# STM32F103_DEBUGGER.net
KiCad netlist of a schematic drawn in Altium Designer
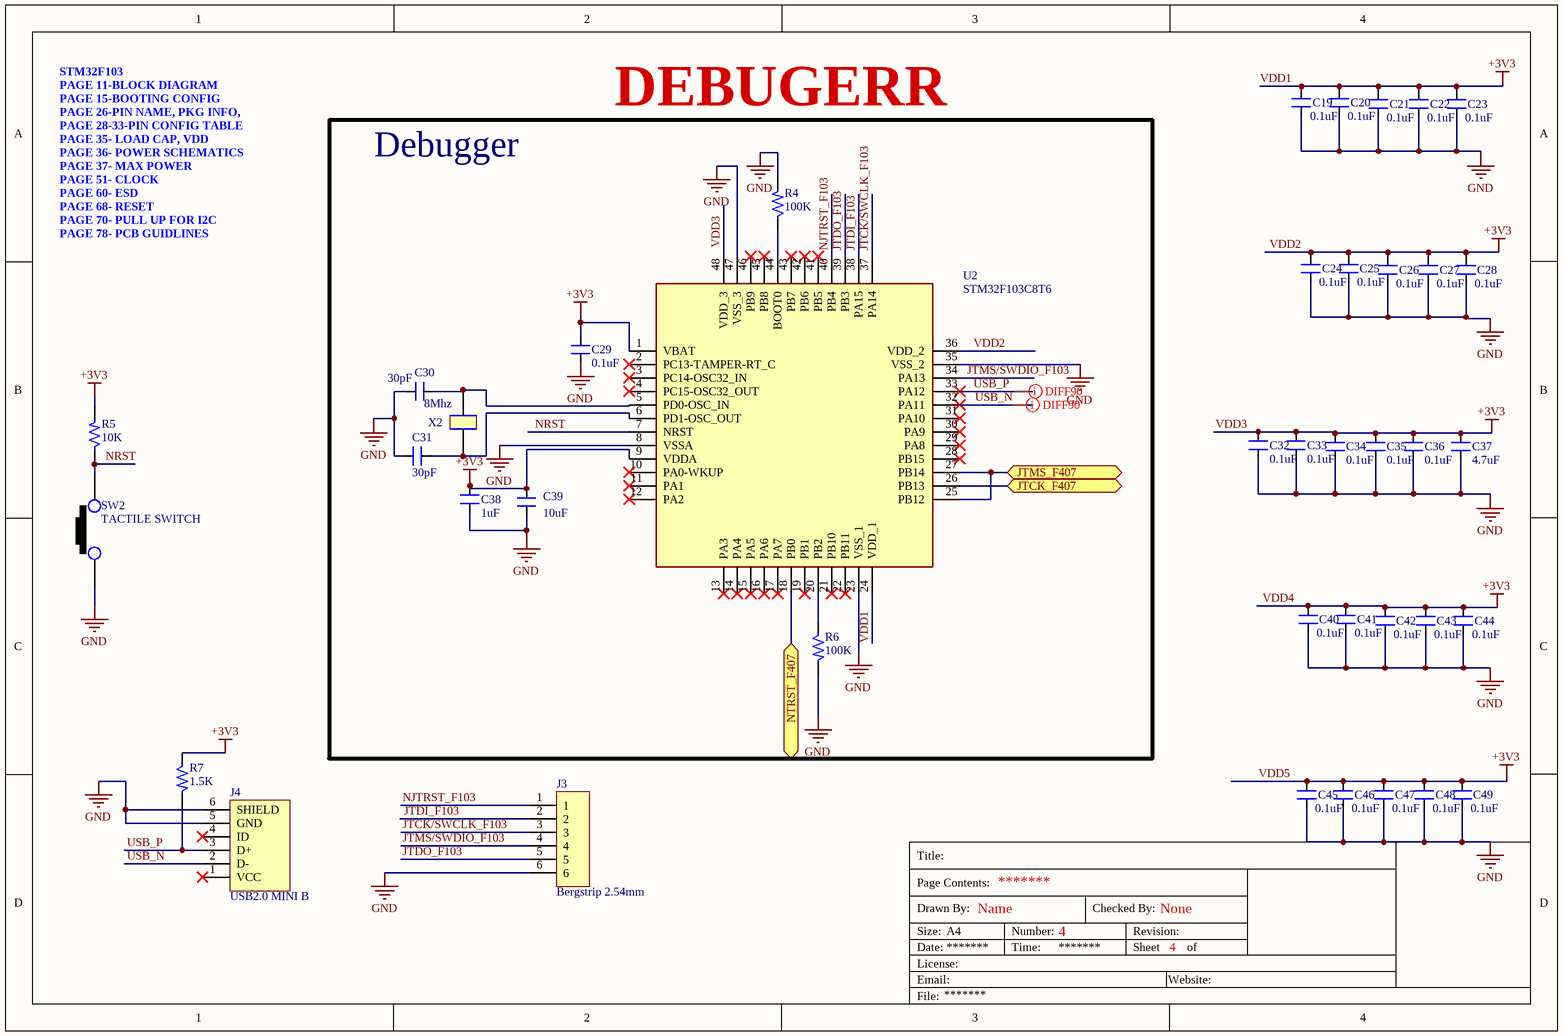
[diagram p0: STM32F103 DEBUGGER.SchDoc]

(export (version "E")
  (design (tool "Eeschema 10.0.6"))
  (components
    (comp (ref "C19")
      (value "0.1uF")
      (footprint "CAP_1206")
      (description "0.1µF ±5% 50V Ceramic Capacitor X7R 1206 (3216 Metric)")
      (fields
        (field (name "MANUFACTURER") "KEMET")
        (field (name "MANUFACTURER PART NUMBER") "C1206C104J5RACTU")
      )
      (libsource (lib "ESTEEMPCBLIB") (part "CAP_0.1uF-50V-5%-1206"))
    )
    (comp (ref "C20")
      (value "0.1uF")
      (footprint "CAP_1206")
      (description "0.1µF ±5% 50V Ceramic Capacitor X7R 1206 (3216 Metric)")
      (fields
        (field (name "MANUFACTURER") "KEMET")
        (field (name "MANUFACTURER PART NUMBER") "C1206C104J5RACTU")
      )
      (libsource (lib "ESTEEMPCBLIB") (part "CAP_0.1uF-50V-5%-1206"))
    )
    (comp (ref "C21")
      (value "0.1uF")
      (footprint "CAP_1206")
      (description "0.1µF ±5% 50V Ceramic Capacitor X7R 1206 (3216 Metric)")
      (fields
        (field (name "MANUFACTURER") "KEMET")
        (field (name "MANUFACTURER PART NUMBER") "C1206C104J5RACTU")
      )
      (libsource (lib "ESTEEMPCBLIB") (part "CAP_0.1uF-50V-5%-1206"))
    )
    (comp (ref "C22")
      (value "0.1uF")
      (footprint "CAP_1206")
      (description "0.1µF ±5% 50V Ceramic Capacitor X7R 1206 (3216 Metric)")
      (fields
        (field (name "MANUFACTURER") "KEMET")
        (field (name "MANUFACTURER PART NUMBER") "C1206C104J5RACTU")
      )
      (libsource (lib "ESTEEMPCBLIB") (part "CAP_0.1uF-50V-5%-1206"))
    )
    (comp (ref "C23")
      (value "0.1uF")
      (footprint "CAP_1206")
      (description "0.1µF ±5% 50V Ceramic Capacitor X7R 1206 (3216 Metric)")
      (fields
        (field (name "MANUFACTURER") "KEMET")
        (field (name "MANUFACTURER PART NUMBER") "C1206C104J5RACTU")
      )
      (libsource (lib "ESTEEMPCBLIB") (part "CAP_0.1uF-50V-5%-1206"))
    )
    (comp (ref "C24")
      (value "0.1uF")
      (footprint "CAP_1206")
      (description "0.1µF ±5% 50V Ceramic Capacitor X7R 1206 (3216 Metric)")
      (fields
        (field (name "MANUFACTURER") "KEMET")
        (field (name "MANUFACTURER PART NUMBER") "C1206C104J5RACTU")
      )
      (libsource (lib "ESTEEMPCBLIB") (part "CAP_0.1uF-50V-5%-1206"))
    )
    (comp (ref "C25")
      (value "0.1uF")
      (footprint "CAP_1206")
      (description "0.1µF ±5% 50V Ceramic Capacitor X7R 1206 (3216 Metric)")
      (fields
        (field (name "MANUFACTURER") "KEMET")
        (field (name "MANUFACTURER PART NUMBER") "C1206C104J5RACTU")
      )
      (libsource (lib "ESTEEMPCBLIB") (part "CAP_0.1uF-50V-5%-1206"))
    )
    (comp (ref "C26")
      (value "0.1uF")
      (footprint "CAP_1206")
      (description "0.1µF ±5% 50V Ceramic Capacitor X7R 1206 (3216 Metric)")
      (fields
        (field (name "MANUFACTURER") "KEMET")
        (field (name "MANUFACTURER PART NUMBER") "C1206C104J5RACTU")
      )
      (libsource (lib "ESTEEMPCBLIB") (part "CAP_0.1uF-50V-5%-1206"))
    )
    (comp (ref "C27")
      (value "0.1uF")
      (footprint "CAP_1206")
      (description "0.1µF ±5% 50V Ceramic Capacitor X7R 1206 (3216 Metric)")
      (fields
        (field (name "MANUFACTURER") "KEMET")
        (field (name "MANUFACTURER PART NUMBER") "C1206C104J5RACTU")
      )
      (libsource (lib "ESTEEMPCBLIB") (part "CAP_0.1uF-50V-5%-1206"))
    )
    (comp (ref "C28")
      (value "0.1uF")
      (footprint "CAP_1206")
      (description "0.1µF ±5% 50V Ceramic Capacitor X7R 1206 (3216 Metric)")
      (fields
        (field (name "MANUFACTURER") "KEMET")
        (field (name "MANUFACTURER PART NUMBER") "C1206C104J5RACTU")
      )
      (libsource (lib "ESTEEMPCBLIB") (part "CAP_0.1uF-50V-5%-1206"))
    )
    (comp (ref "C29")
      (value "0.1uF")
      (footprint "CAP_0805")
      (description "0.1µF ±10% 50V Ceramic Capacitor X7R 0805 (2012 Metric)")
      (fields
        (field (name "MANUFACTURER") "Samsung")
        (field (name "MANUFACTURER PART NUMBER") "CL21B104KBCNNNC")
      )
      (libsource (lib "ESTEEMPCBLIB") (part "CAP_0.1uF-50V-10%-0805"))
    )
    (comp (ref "C30")
      (value "30pF")
      (footprint "CAP_0805")
      (description "±10% 50V Ceramic Capacitor C0G, NP0 0805 (2012 Metric)")
      (fields
        (field (name "MANUFACTURER PART NUMBER") "C0805C300K5GAC7800")
        (field (name "MANUFACTURER") "KEMET")
      )
      (libsource (lib "ESTEEMPCBLIB") (part "CAP_30pF-50V-10%-0805"))
    )
    (comp (ref "C31")
      (value "30pF")
      (footprint "CAP_0805")
      (description "±10% 50V Ceramic Capacitor C0G, NP0 0805 (2012 Metric)")
      (fields
        (field (name "MANUFACTURER PART NUMBER") "C0805C300K5GAC7800")
        (field (name "MANUFACTURER") "KEMET")
      )
      (libsource (lib "ESTEEMPCBLIB") (part "CAP_30pF-50V-10%-0805"))
    )
    (comp (ref "C32")
      (value "0.1uF")
      (footprint "CAP_1206")
      (description "0.1µF ±5% 50V Ceramic Capacitor X7R 1206 (3216 Metric)")
      (fields
        (field (name "MANUFACTURER") "KEMET")
        (field (name "MANUFACTURER PART NUMBER") "C1206C104J5RACTU")
      )
      (libsource (lib "ESTEEMPCBLIB") (part "CAP_0.1uF-50V-5%-1206"))
    )
    (comp (ref "C33")
      (value "0.1uF")
      (footprint "CAP_1206")
      (description "0.1µF ±5% 50V Ceramic Capacitor X7R 1206 (3216 Metric)")
      (fields
        (field (name "MANUFACTURER") "KEMET")
        (field (name "MANUFACTURER PART NUMBER") "C1206C104J5RACTU")
      )
      (libsource (lib "ESTEEMPCBLIB") (part "CAP_0.1uF-50V-5%-1206"))
    )
    (comp (ref "C34")
      (value "0.1uF")
      (footprint "CAP_1206")
      (description "0.1µF ±5% 50V Ceramic Capacitor X7R 1206 (3216 Metric)")
      (fields
        (field (name "MANUFACTURER") "KEMET")
        (field (name "MANUFACTURER PART NUMBER") "C1206C104J5RACTU")
      )
      (libsource (lib "ESTEEMPCBLIB") (part "CAP_0.1uF-50V-5%-1206"))
    )
    (comp (ref "C35")
      (value "0.1uF")
      (footprint "CAP_1206")
      (description "0.1µF ±5% 50V Ceramic Capacitor X7R 1206 (3216 Metric)")
      (fields
        (field (name "MANUFACTURER") "KEMET")
        (field (name "MANUFACTURER PART NUMBER") "C1206C104J5RACTU")
      )
      (libsource (lib "ESTEEMPCBLIB") (part "CAP_0.1uF-50V-5%-1206"))
    )
    (comp (ref "C36")
      (value "0.1uF")
      (footprint "CAP_1206")
      (description "0.1µF ±5% 50V Ceramic Capacitor X7R 1206 (3216 Metric)")
      (fields
        (field (name "MANUFACTURER") "KEMET")
        (field (name "MANUFACTURER PART NUMBER") "C1206C104J5RACTU")
      )
      (libsource (lib "ESTEEMPCBLIB") (part "CAP_0.1uF-50V-5%-1206"))
    )
    (comp (ref "C37")
      (value "4.7uF")
      (footprint "CAP_0805")
      (description "4.7µF ±10% 50V Ceramic Capacitor X5R 0805 (2012 Metric)")
      (fields
        (field (name "MANUFACTURER") "Yageo")
        (field (name "MANUFACTURER PART NUMBER") "GRM21BR61H475KE51L")
      )
      (libsource (lib "ESTEEMPCBLIB") (part "CAP_4.7uF-50V-10%-0805"))
    )
    (comp (ref "C38")
      (value "1uF")
      (footprint "CAP_0805")
      (description "1µF ±5% 50V Ceramic Capacitor X7R 0805 (2012 Metric)")
      (fields
        (field (name "MANUFACTURER") "Samsung")
        (field (name "MANUFACTURER PART NUMBER") "CC0805JKX7R9BB105")
      )
      (libsource (lib "ESTEEMPCBLIB") (part "CAP_1uF-50V-5%-0805"))
    )
    (comp (ref "C39")
      (value "10uF")
      (footprint "CAP_1206")
      (description "10µF ±10% 50V Ceramic Capacitor X7R 1206 (3216 Metric)")
      (fields
        (field (name "MANUFACTURER") "KEMET")
        (field (name "MANUFACTURER PART NUMBER") "CL31B106KBHNNNE")
      )
      (libsource (lib "ESTEEMPCBLIB") (part "CAP_10uF-50V-10%-1206"))
    )
    (comp (ref "C40")
      (value "0.1uF")
      (footprint "CAP_1206")
      (description "0.1µF ±5% 50V Ceramic Capacitor X7R 1206 (3216 Metric)")
      (fields
        (field (name "MANUFACTURER") "KEMET")
        (field (name "MANUFACTURER PART NUMBER") "C1206C104J5RACTU")
      )
      (libsource (lib "ESTEEMPCBLIB") (part "CAP_0.1uF-50V-5%-1206"))
    )
    (comp (ref "C41")
      (value "0.1uF")
      (footprint "CAP_1206")
      (description "0.1µF ±5% 50V Ceramic Capacitor X7R 1206 (3216 Metric)")
      (fields
        (field (name "MANUFACTURER") "KEMET")
        (field (name "MANUFACTURER PART NUMBER") "C1206C104J5RACTU")
      )
      (libsource (lib "ESTEEMPCBLIB") (part "CAP_0.1uF-50V-5%-1206"))
    )
    (comp (ref "C42")
      (value "0.1uF")
      (footprint "CAP_1206")
      (description "0.1µF ±5% 50V Ceramic Capacitor X7R 1206 (3216 Metric)")
      (fields
        (field (name "MANUFACTURER") "KEMET")
        (field (name "MANUFACTURER PART NUMBER") "C1206C104J5RACTU")
      )
      (libsource (lib "ESTEEMPCBLIB") (part "CAP_0.1uF-50V-5%-1206"))
    )
    (comp (ref "C43")
      (value "0.1uF")
      (footprint "CAP_1206")
      (description "0.1µF ±5% 50V Ceramic Capacitor X7R 1206 (3216 Metric)")
      (fields
        (field (name "MANUFACTURER") "KEMET")
        (field (name "MANUFACTURER PART NUMBER") "C1206C104J5RACTU")
      )
      (libsource (lib "ESTEEMPCBLIB") (part "CAP_0.1uF-50V-5%-1206"))
    )
    (comp (ref "C44")
      (value "0.1uF")
      (footprint "CAP_1206")
      (description "0.1µF ±5% 50V Ceramic Capacitor X7R 1206 (3216 Metric)")
      (fields
        (field (name "MANUFACTURER") "KEMET")
        (field (name "MANUFACTURER PART NUMBER") "C1206C104J5RACTU")
      )
      (libsource (lib "ESTEEMPCBLIB") (part "CAP_0.1uF-50V-5%-1206"))
    )
    (comp (ref "C45")
      (value "0.1uF")
      (footprint "CAP_1206")
      (description "0.1µF ±5% 50V Ceramic Capacitor X7R 1206 (3216 Metric)")
      (fields
        (field (name "MANUFACTURER") "KEMET")
        (field (name "MANUFACTURER PART NUMBER") "C1206C104J5RACTU")
      )
      (libsource (lib "ESTEEMPCBLIB") (part "CAP_0.1uF-50V-5%-1206"))
    )
    (comp (ref "C46")
      (value "0.1uF")
      (footprint "CAP_1206")
      (description "0.1µF ±5% 50V Ceramic Capacitor X7R 1206 (3216 Metric)")
      (fields
        (field (name "MANUFACTURER") "KEMET")
        (field (name "MANUFACTURER PART NUMBER") "C1206C104J5RACTU")
      )
      (libsource (lib "ESTEEMPCBLIB") (part "CAP_0.1uF-50V-5%-1206"))
    )
    (comp (ref "C47")
      (value "0.1uF")
      (footprint "CAP_1206")
      (description "0.1µF ±5% 50V Ceramic Capacitor X7R 1206 (3216 Metric)")
      (fields
        (field (name "MANUFACTURER") "KEMET")
        (field (name "MANUFACTURER PART NUMBER") "C1206C104J5RACTU")
      )
      (libsource (lib "ESTEEMPCBLIB") (part "CAP_0.1uF-50V-5%-1206"))
    )
    (comp (ref "C48")
      (value "0.1uF")
      (footprint "CAP_1206")
      (description "0.1µF ±5% 50V Ceramic Capacitor X7R 1206 (3216 Metric)")
      (fields
        (field (name "MANUFACTURER") "KEMET")
        (field (name "MANUFACTURER PART NUMBER") "C1206C104J5RACTU")
      )
      (libsource (lib "ESTEEMPCBLIB") (part "CAP_0.1uF-50V-5%-1206"))
    )
    (comp (ref "C49")
      (value "0.1uF")
      (footprint "CAP_1206")
      (description "0.1µF ±5% 50V Ceramic Capacitor X7R 1206 (3216 Metric)")
      (fields
        (field (name "MANUFACTURER") "KEMET")
        (field (name "MANUFACTURER PART NUMBER") "C1206C104J5RACTU")
      )
      (libsource (lib "ESTEEMPCBLIB") (part "CAP_0.1uF-50V-5%-1206"))
    )
    (comp (ref "J3")
      (value "Bergstrip 2.54mm")
      (footprint "CON6_100_59D78_TH_ST")
      (description "6 Pins, 1 Row 2.54mm Pitch, Straight bergstrip, Female")
      (fields (field (name "MANUFACTURER") "Molex") (field (name "MANUFACTURER PART NUMBER") "22-10-2061"))
      (libsource (lib "ESTEEMPCBLIB") (part "CON-BS-SKT_6X1-100-ST-TH"))
    )
    (comp (ref "J4")
      (value "USB2.0 MINI B")
      (footprint "CON_690-005-299-043")
      (description "USB - mini B USB 2.0 Receptacle Connector 5 Position Surface Mount, Right Angle")
      (fields
        (field (name "MANUFACTURER") "EDAC")
        (field (name "MANUFACTURER PART NUMBER") "690-005-299-043")
      )
      (libsource (lib "ESTEEMPCBLIB") (part "CON_USB2.0-MINIB-SMD"))
    )
    (comp (ref "R4")
      (value "100K")
      (footprint "RES_0603")
      (description "100 kOhms ±1% 0.1W, 1/10W Chip Resistor 0603 (1608 Metric) Automotive AEC-Q200 Thick Film")
      (fields
        (field (name "MANUFACTURER") "Stackpole Electronics")
        (field (name "MANUFACTURER PART NUMBER") "RMCF0603FT100K")
      )
      (libsource (lib "ESTEEMPCBLIB") (part "RES_100K-0.1W-1%-0603"))
    )
    (comp (ref "R5")
      (value "10K")
      (footprint "RES_0603")
      (description "10 kOhms ±1% 0.1W, 1/10W Chip Resistor 0603 (1608 Metric) Automotive AEC-Q200 Thick Film")
      (fields (field (name "MANUFACTURER") "Walsin") (field (name "MANUFACTURER PART NUMBER") "WR06X1002FTL"))
      (libsource (lib "ESTEEMPCBLIB") (part "RES_10K-0.1W-1%-0603"))
    )
    (comp (ref "R6")
      (value "100K")
      (footprint "RES_0603")
      (description "100 kOhms ±1% 0.1W, 1/10W Chip Resistor 0603 (1608 Metric) Automotive AEC-Q200 Thick Film")
      (fields
        (field (name "MANUFACTURER") "Stackpole Electronics")
        (field (name "MANUFACTURER PART NUMBER") "RMCF0603FT100K")
      )
      (libsource (lib "ESTEEMPCBLIB") (part "RES_100K-0.1W-1%-0603"))
    )
    (comp (ref "R7")
      (value "1.5K")
      (footprint "RES_0805")
      (description "1.5 kOhms ±1% 0.125W, 1/8W Chip Resistor 0805 (2012 Metric) Thick Film")
      (fields
        (field (name "MANUFACTURER") "TE Connectivity Passive Product")
        (field (name "MANUFACTURER PART NUMBER") "CRG0805F1K5")
      )
      (libsource (lib "ESTEEMPCBLIB") (part "RES_1.5K-0.125W-1%-0805"))
    )
    (comp (ref "SW2")
      (value "TACTILE SWITCH")
      (footprint "SW_342_SMD")
      (description "Tactile Switch SPST-NO Top Actuated Surface Mount")
      (fields
        (field (name "MANUFACTURER") "ITT C&K")
        (field (name "MANUFACTURER PART NUMBER") "RS-282G05A3-SMRT")
      )
      (libsource (lib "ESTEEMPCBLIB") (part "SW1_RS-282G05A3-SMRT-SMD"))
    )
    (comp (ref "U2")
      (value "STM32F103C8T6")
      (footprint "LQFP-48_19.6_393_58X11_SMD")
      (description "ARM® Cortex®-M3 STM32F1 Microcontroller IC 32-Bit 72MHz 64KB (64K x 8) FLASH 48-LQFP (7x7)")
      (fields (field (name "MANUFACTURER") "STMicroelectronics"))
      (libsource (lib "ESTEEMPCBLIB") (part "IC_STM32F103C8T6"))
    )
    (comp (ref "X2")
      (value "8Mhz")
      (footprint "XTAL_314_240X47_SMD")
      (description "8MHz ±30ppm Crystal 32pF 60 Ohms HC-49/US")
      (fields
        (field (name "MANUFACTURER") "Fox Electronics")
        (field (name "MANUFACTURER PART NUMBER") "ECS-80-32-5PX-TR")
      )
      (libsource (lib "ESTEEMPCBLIB") (part "XTAL_8MHZ-ECS-80-32-5PX-SMD"))
    )
  )
  (nets
    (net (code "1") (name "+3V3") (class "Default")
      (node (ref "C19") (pin "2") (pinfunction "2_2") (pintype "passive"))
      (node (ref "C20") (pin "2") (pinfunction "2_2") (pintype "passive"))
      (node (ref "C21") (pin "2") (pinfunction "2_2") (pintype "passive"))
      (node (ref "C22") (pin "2") (pinfunction "2_2") (pintype "passive"))
      (node (ref "C23") (pin "2") (pinfunction "2_2") (pintype "passive"))
      (node (ref "C24") (pin "2") (pinfunction "2_2") (pintype "passive"))
      (node (ref "C25") (pin "2") (pinfunction "2_2") (pintype "passive"))
      (node (ref "C26") (pin "2") (pinfunction "2_2") (pintype "passive"))
      (node (ref "C27") (pin "2") (pinfunction "2_2") (pintype "passive"))
      (node (ref "C28") (pin "2") (pinfunction "2_2") (pintype "passive"))
      (node (ref "C29") (pin "2") (pinfunction "2_2") (pintype "passive"))
      (node (ref "C32") (pin "2") (pinfunction "2_2") (pintype "passive"))
      (node (ref "C33") (pin "2") (pinfunction "2_2") (pintype "passive"))
      (node (ref "C34") (pin "2") (pinfunction "2_2") (pintype "passive"))
      (node (ref "C35") (pin "2") (pinfunction "2_2") (pintype "passive"))
      (node (ref "C36") (pin "2") (pinfunction "2_2") (pintype "passive"))
      (node (ref "C37") (pin "2") (pinfunction "2_2") (pintype "passive"))
      (node (ref "C38") (pin "2") (pinfunction "2_2") (pintype "passive"))
      (node (ref "C39") (pin "2") (pinfunction "2_2") (pintype "passive"))
      (node (ref "C40") (pin "2") (pinfunction "2_2") (pintype "passive"))
      (node (ref "C41") (pin "2") (pinfunction "2_2") (pintype "passive"))
      (node (ref "C42") (pin "2") (pinfunction "2_2") (pintype "passive"))
      (node (ref "C43") (pin "2") (pinfunction "2_2") (pintype "passive"))
      (node (ref "C44") (pin "2") (pinfunction "2_2") (pintype "passive"))
      (node (ref "C45") (pin "2") (pinfunction "2_2") (pintype "passive"))
      (node (ref "C46") (pin "2") (pinfunction "2_2") (pintype "passive"))
      (node (ref "C47") (pin "2") (pinfunction "2_2") (pintype "passive"))
      (node (ref "C48") (pin "2") (pinfunction "2_2") (pintype "passive"))
      (node (ref "C49") (pin "2") (pinfunction "2_2") (pintype "passive"))
      (node (ref "R5") (pin "2") (pinfunction "2_2") (pintype "passive"))
      (node (ref "R7") (pin "1") (pinfunction "1_1") (pintype "passive"))
      (node (ref "U2") (pin "1") (pinfunction "VBAT_1") (pintype "passive"))
      (node (ref "U2") (pin "24") (pinfunction "VDD_1_24") (pintype "passive"))
      (node (ref "U2") (pin "36") (pinfunction "VDD_2_36") (pintype "passive"))
      (node (ref "U2") (pin "48") (pinfunction "VDD_3_48") (pintype "passive"))
      (node (ref "U2") (pin "9") (pinfunction "VDDA_9") (pintype "passive"))
    )
    (net (code "2") (name "/JTCK_F407") (class "Default")
      (node (ref "U2") (pin "26") (pinfunction "PB13_26") (pintype "passive"))
    )
    (net (code "3") (name "/JTCK{slash}SWCLK_F103") (class "Default")
      (node (ref "J3") (pin "3") (pinfunction "3_3") (pintype "passive"))
      (node (ref "U2") (pin "37") (pinfunction "PA14_37") (pintype "passive"))
    )
    (net (code "4") (name "/JTDI_F103") (class "Default")
      (node (ref "J3") (pin "2") (pinfunction "2_2") (pintype "passive"))
      (node (ref "U2") (pin "38") (pinfunction "PA15_38") (pintype "passive"))
    )
    (net (code "5") (name "/JTDO_F103") (class "Default")
      (node (ref "J3") (pin "5") (pinfunction "5_5") (pintype "passive"))
      (node (ref "U2") (pin "39") (pinfunction "PB3_39") (pintype "passive"))
    )
    (net (code "6") (name "/JTMS_F407") (class "Default")
      (node (ref "U2") (pin "25") (pinfunction "PB12_25") (pintype "passive"))
      (node (ref "U2") (pin "27") (pinfunction "PB14_27") (pintype "passive"))
    )
    (net (code "7") (name "/JTMS{slash}SWDIO_F103") (class "Default")
      (node (ref "J3") (pin "4") (pinfunction "4_4") (pintype "passive"))
      (node (ref "U2") (pin "34") (pinfunction "PA13_34") (pintype "passive"))
    )
    (net (code "8") (name "/NJTRST_F103") (class "Default")
      (node (ref "J3") (pin "1") (pinfunction "1_1") (pintype "passive"))
      (node (ref "U2") (pin "40") (pinfunction "PB4_40") (pintype "passive"))
    )
    (net (code "9") (name "/NRST") (class "Default")
      (node (ref "R5") (pin "1") (pinfunction "1_1") (pintype "passive"))
      (node (ref "SW2") (pin "2") (pinfunction "2_2") (pintype "passive"))
      (node (ref "U2") (pin "7") (pinfunction "NRST_7") (pintype "passive"))
    )
    (net (code "10") (name "/NTRST_F407") (class "Default")
      (node (ref "U2") (pin "18") (pinfunction "PB0_18") (pintype "passive"))
    )
    (net (code "11") (name "/USB_N") (class "Default")
      (node (ref "J4") (pin "2") (pinfunction "D-_2") (pintype "passive"))
      (node (ref "U2") (pin "32") (pinfunction "PA11_32") (pintype "passive"))
    )
    (net (code "12") (name "/USB_P") (class "Default")
      (node (ref "J4") (pin "3") (pinfunction "D+_3") (pintype "passive"))
      (node (ref "R7") (pin "2") (pinfunction "2_2") (pintype "passive"))
      (node (ref "U2") (pin "33") (pinfunction "PA12_33") (pintype "passive"))
    )
    (net (code "13") (name "GND") (class "Default")
      (node (ref "C19") (pin "1") (pinfunction "1_1") (pintype "passive"))
      (node (ref "C20") (pin "1") (pinfunction "1_1") (pintype "passive"))
      (node (ref "C21") (pin "1") (pinfunction "1_1") (pintype "passive"))
      (node (ref "C22") (pin "1") (pinfunction "1_1") (pintype "passive"))
      (node (ref "C23") (pin "1") (pinfunction "1_1") (pintype "passive"))
      (node (ref "C24") (pin "1") (pinfunction "1_1") (pintype "passive"))
      (node (ref "C25") (pin "1") (pinfunction "1_1") (pintype "passive"))
      (node (ref "C26") (pin "1") (pinfunction "1_1") (pintype "passive"))
      (node (ref "C27") (pin "1") (pinfunction "1_1") (pintype "passive"))
      (node (ref "C28") (pin "1") (pinfunction "1_1") (pintype "passive"))
      (node (ref "C29") (pin "1") (pinfunction "1_1") (pintype "passive"))
      (node (ref "C30") (pin "1") (pinfunction "1_1") (pintype "passive"))
      (node (ref "C31") (pin "1") (pinfunction "1_1") (pintype "passive"))
      (node (ref "C32") (pin "1") (pinfunction "1_1") (pintype "passive"))
      (node (ref "C33") (pin "1") (pinfunction "1_1") (pintype "passive"))
      (node (ref "C34") (pin "1") (pinfunction "1_1") (pintype "passive"))
      (node (ref "C35") (pin "1") (pinfunction "1_1") (pintype "passive"))
      (node (ref "C36") (pin "1") (pinfunction "1_1") (pintype "passive"))
      (node (ref "C37") (pin "1") (pinfunction "1_1") (pintype "passive"))
      (node (ref "C38") (pin "1") (pinfunction "1_1") (pintype "passive"))
      (node (ref "C39") (pin "1") (pinfunction "1_1") (pintype "passive"))
      (node (ref "C40") (pin "1") (pinfunction "1_1") (pintype "passive"))
      (node (ref "C41") (pin "1") (pinfunction "1_1") (pintype "passive"))
      (node (ref "C42") (pin "1") (pinfunction "1_1") (pintype "passive"))
      (node (ref "C43") (pin "1") (pinfunction "1_1") (pintype "passive"))
      (node (ref "C44") (pin "1") (pinfunction "1_1") (pintype "passive"))
      (node (ref "C45") (pin "1") (pinfunction "1_1") (pintype "passive"))
      (node (ref "C46") (pin "1") (pinfunction "1_1") (pintype "passive"))
      (node (ref "C47") (pin "1") (pinfunction "1_1") (pintype "passive"))
      (node (ref "C48") (pin "1") (pinfunction "1_1") (pintype "passive"))
      (node (ref "C49") (pin "1") (pinfunction "1_1") (pintype "passive"))
      (node (ref "J3") (pin "6") (pinfunction "6_6") (pintype "passive"))
      (node (ref "J4") (pin "5") (pinfunction "GND_5") (pintype "passive"))
      (node (ref "J4") (pin "6") (pinfunction "SHIELD_6") (pintype "passive"))
      (node (ref "R4") (pin "2") (pinfunction "2_2") (pintype "passive"))
      (node (ref "R6") (pin "2") (pinfunction "2_2") (pintype "passive"))
      (node (ref "SW2") (pin "1") (pinfunction "1_1") (pintype "passive"))
      (node (ref "U2") (pin "23") (pinfunction "VSS_1_23") (pintype "passive"))
      (node (ref "U2") (pin "35") (pinfunction "VSS_2_35") (pintype "passive"))
      (node (ref "U2") (pin "47") (pinfunction "VSS_3_47") (pintype "passive"))
      (node (ref "U2") (pin "8") (pinfunction "VSSA_8") (pintype "passive"))
    )
    (net (code "14") (name "Net-(U2-BOOT0)") (class "Default")
      (node (ref "R4") (pin "1") (pinfunction "1_1") (pintype "passive"))
      (node (ref "U2") (pin "44") (pinfunction "BOOT0_44") (pintype "passive"))
    )
    (net (code "15") (name "Net-(U2-PB2)") (class "Default")
      (node (ref "R6") (pin "1") (pinfunction "1_1") (pintype "passive"))
      (node (ref "U2") (pin "20") (pinfunction "PB2_20") (pintype "passive"))
    )
    (net (code "16") (name "Net-(U2-PD0-OSC_IN)") (class "Default")
      (node (ref "C30") (pin "2") (pinfunction "2_2") (pintype "passive"))
      (node (ref "U2") (pin "5") (pinfunction "PD0-OSC_IN_5") (pintype "passive"))
      (node (ref "X2") (pin "2") (pinfunction "2_2") (pintype "passive"))
    )
    (net (code "17") (name "Net-(U2-PD1-OSC_OUT)") (class "Default")
      (node (ref "C31") (pin "2") (pinfunction "2_2") (pintype "passive"))
      (node (ref "U2") (pin "6") (pinfunction "PD1-OSC_OUT_6") (pintype "passive"))
      (node (ref "X2") (pin "1") (pinfunction "1_1") (pintype "passive"))
    )
    (net (code "18") (name "unconnected-(J4-ID-Pad4)") (class "Default")
      (node (ref "J4") (pin "4") (pinfunction "ID_4") (pintype "passive+no_connect"))
    )
    (net (code "19") (name "unconnected-(J4-VCC-Pad1)") (class "Default")
      (node (ref "J4") (pin "1") (pinfunction "VCC_1") (pintype "passive+no_connect"))
    )
    (net (code "20") (name "unconnected-(U2-PA0-WKUP-Pad10)") (class "Default")
      (node (ref "U2") (pin "10") (pinfunction "PA0-WKUP_10") (pintype "passive+no_connect"))
    )
    (net (code "21") (name "unconnected-(U2-PA1-Pad11)") (class "Default")
      (node (ref "U2") (pin "11") (pinfunction "PA1_11") (pintype "passive+no_connect"))
    )
    (net (code "22") (name "unconnected-(U2-PA2-Pad12)") (class "Default")
      (node (ref "U2") (pin "12") (pinfunction "PA2_12") (pintype "passive+no_connect"))
    )
    (net (code "23") (name "unconnected-(U2-PA3-Pad13)") (class "Default")
      (node (ref "U2") (pin "13") (pinfunction "PA3_13") (pintype "passive+no_connect"))
    )
    (net (code "24") (name "unconnected-(U2-PA4-Pad14)") (class "Default")
      (node (ref "U2") (pin "14") (pinfunction "PA4_14") (pintype "passive+no_connect"))
    )
    (net (code "25") (name "unconnected-(U2-PA5-Pad15)") (class "Default")
      (node (ref "U2") (pin "15") (pinfunction "PA5_15") (pintype "passive+no_connect"))
    )
    (net (code "26") (name "unconnected-(U2-PA6-Pad16)") (class "Default")
      (node (ref "U2") (pin "16") (pinfunction "PA6_16") (pintype "passive+no_connect"))
    )
    (net (code "27") (name "unconnected-(U2-PA7-Pad17)") (class "Default")
      (node (ref "U2") (pin "17") (pinfunction "PA7_17") (pintype "passive+no_connect"))
    )
    (net (code "28") (name "unconnected-(U2-PA8-Pad29)") (class "Default")
      (node (ref "U2") (pin "29") (pinfunction "PA8_29") (pintype "passive+no_connect"))
    )
    (net (code "29") (name "unconnected-(U2-PA9-Pad30)") (class "Default")
      (node (ref "U2") (pin "30") (pinfunction "PA9_30") (pintype "passive+no_connect"))
    )
    (net (code "30") (name "unconnected-(U2-PA10-Pad31)") (class "Default")
      (node (ref "U2") (pin "31") (pinfunction "PA10_31") (pintype "passive+no_connect"))
    )
    (net (code "31") (name "unconnected-(U2-PB1-Pad19)") (class "Default")
      (node (ref "U2") (pin "19") (pinfunction "PB1_19") (pintype "passive+no_connect"))
    )
    (net (code "32") (name "unconnected-(U2-PB5-Pad41)") (class "Default")
      (node (ref "U2") (pin "41") (pinfunction "PB5_41") (pintype "passive+no_connect"))
    )
    (net (code "33") (name "unconnected-(U2-PB6-Pad42)") (class "Default")
      (node (ref "U2") (pin "42") (pinfunction "PB6_42") (pintype "passive+no_connect"))
    )
    (net (code "34") (name "unconnected-(U2-PB7-Pad43)") (class "Default")
      (node (ref "U2") (pin "43") (pinfunction "PB7_43") (pintype "passive+no_connect"))
    )
    (net (code "35") (name "unconnected-(U2-PB8-Pad45)") (class "Default")
      (node (ref "U2") (pin "45") (pinfunction "PB8_45") (pintype "passive+no_connect"))
    )
    (net (code "36") (name "unconnected-(U2-PB9-Pad46)") (class "Default")
      (node (ref "U2") (pin "46") (pinfunction "PB9_46") (pintype "passive+no_connect"))
    )
    (net (code "37") (name "unconnected-(U2-PB10-Pad21)") (class "Default")
      (node (ref "U2") (pin "21") (pinfunction "PB10_21") (pintype "passive+no_connect"))
    )
    (net (code "38") (name "unconnected-(U2-PB11-Pad22)") (class "Default")
      (node (ref "U2") (pin "22") (pinfunction "PB11_22") (pintype "passive+no_connect"))
    )
    (net (code "39") (name "unconnected-(U2-PB15-Pad28)") (class "Default")
      (node (ref "U2") (pin "28") (pinfunction "PB15_28") (pintype "passive+no_connect"))
    )
    (net (code "40") (name "unconnected-(U2-PC13-TAMPER-RT_C-Pad2)") (class "Default")
      (node (ref "U2") (pin "2") (pinfunction "PC13-TAMPER-RT_C_2") (pintype "passive+no_connect"))
    )
    (net (code "41") (name "unconnected-(U2-PC14-OSC32_IN-Pad3)") (class "Default")
      (node (ref "U2") (pin "3") (pinfunction "PC14-OSC32_IN_3") (pintype "passive+no_connect"))
    )
    (net (code "42") (name "unconnected-(U2-PC15-OSC32_OUT-Pad4)") (class "Default")
      (node (ref "U2") (pin "4") (pinfunction "PC15-OSC32_OUT_4") (pintype "passive+no_connect"))
    )
  )
)
